# bootloader_burner.net
KiCad netlist of a schematic drawn in EAGLE
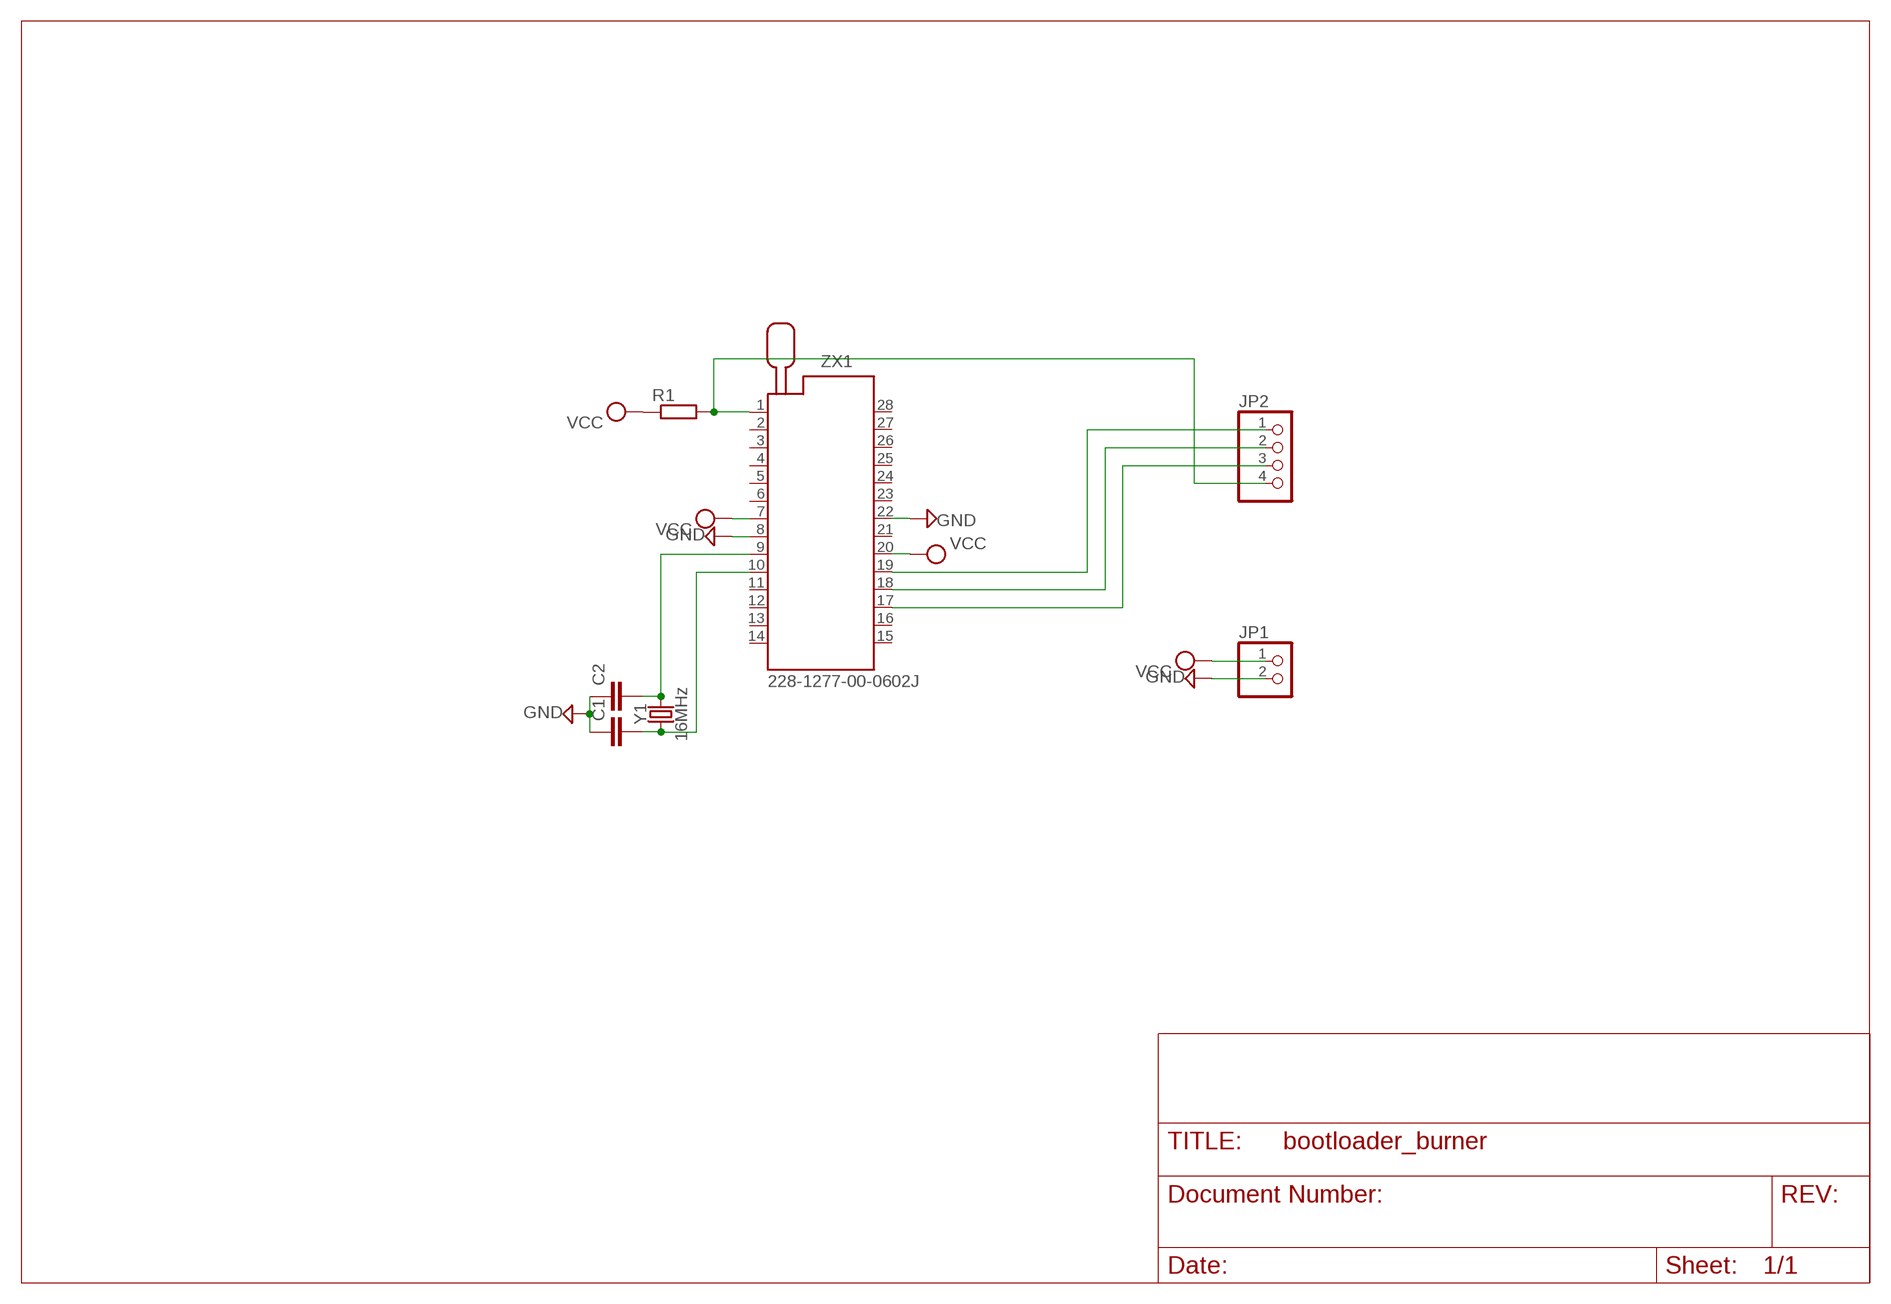
[diagram p0: schematic, sheet 1]

(export (version "E")
  (design (tool "Eeschema 10.0.6"))
  (components
    (comp (ref "C1")
      (value "C-EU025-025X050")
      (footprint "eagle-import:C025-025X050")
      (libsource (lib "eagle-import") (part "C-EU025-025X050"))
    )
    (comp (ref "C2")
      (value "C-EU025-025X050")
      (footprint "eagle-import:C025-025X050")
      (libsource (lib "eagle-import") (part "C-EU025-025X050"))
    )
    (comp (ref "JP1")
      (value "PINHD-1X2")
      (footprint "eagle-import:1X02")
      (libsource (lib "eagle-import") (part "PINHD-1X2"))
    )
    (comp (ref "JP2")
      (value "PINHD-1X4")
      (footprint "eagle-import:1X04")
      (libsource (lib "eagle-import") (part "PINHD-1X4"))
    )
    (comp (ref "R1")
      (value "R-EU_0207/10")
      (footprint "eagle-import:0207_10")
      (libsource (lib "eagle-import") (part "R-EU_0207/10"))
    )
    (comp (ref "Y1")
      (value "16MHz")
      (footprint "eagle-import:HC49US")
      (libsource (lib "eagle-import") (part "CRYSTAL-16MHZPTH-HC49US"))
    )
    (comp (ref "ZX1")
      (value "228-1277-00-0602J")
      (footprint "eagle-import:228-1277-00-0602J")
      (fields (field (name "MF") "3M"))
      (libsource (lib "eagle-import") (part "228-?00-0602J1277-"))
    )
  )
  (nets
    (net (code "1") (name "GND") (class "Default")
      (node (ref "C1") (pin "1") (pinfunction "1_1") (pintype "passive"))
      (node (ref "C2") (pin "1") (pinfunction "1_1") (pintype "passive"))
      (node (ref "JP1") (pin "2") (pinfunction "2_2") (pintype "passive"))
      (node (ref "ZX1") (pin "22") (pinfunction "22_22") (pintype "passive"))
      (node (ref "ZX1") (pin "8") (pinfunction "8_8") (pintype "passive"))
    )
    (net (code "2") (name "Net-(C1-Pad2)") (class "Default")
      (node (ref "C1") (pin "2") (pinfunction "2_2") (pintype "passive"))
      (node (ref "Y1") (pin "1") (pinfunction "1_1") (pintype "passive"))
      (node (ref "ZX1") (pin "10") (pinfunction "10_10") (pintype "passive"))
    )
    (net (code "3") (name "Net-(C2-Pad2)") (class "Default")
      (node (ref "C2") (pin "2") (pinfunction "2_2") (pintype "passive"))
      (node (ref "Y1") (pin "2") (pinfunction "2_2") (pintype "passive"))
      (node (ref "ZX1") (pin "9") (pinfunction "9_9") (pintype "passive"))
    )
    (net (code "4") (name "Net-(JP2-Pad1)") (class "Default")
      (node (ref "JP2") (pin "1") (pinfunction "1_1") (pintype "passive"))
      (node (ref "ZX1") (pin "19") (pinfunction "19_19") (pintype "passive"))
    )
    (net (code "5") (name "Net-(JP2-Pad2)") (class "Default")
      (node (ref "JP2") (pin "2") (pinfunction "2_2") (pintype "passive"))
      (node (ref "ZX1") (pin "18") (pinfunction "18_18") (pintype "passive"))
    )
    (net (code "6") (name "Net-(JP2-Pad3)") (class "Default")
      (node (ref "JP2") (pin "3") (pinfunction "3_3") (pintype "passive"))
      (node (ref "ZX1") (pin "17") (pinfunction "17_17") (pintype "passive"))
    )
    (net (code "7") (name "Net-(JP2-Pad4)") (class "Default")
      (node (ref "JP2") (pin "4") (pinfunction "4_4") (pintype "passive"))
      (node (ref "R1") (pin "2") (pinfunction "2_2") (pintype "passive"))
      (node (ref "ZX1") (pin "1") (pinfunction "1_1") (pintype "passive"))
    )
    (net (code "8") (name "VCC") (class "Default")
      (node (ref "JP1") (pin "1") (pinfunction "1_1") (pintype "passive"))
      (node (ref "R1") (pin "1") (pinfunction "1_1") (pintype "passive"))
      (node (ref "ZX1") (pin "20") (pinfunction "20_20") (pintype "passive"))
      (node (ref "ZX1") (pin "7") (pinfunction "7_7") (pintype "passive"))
    )
    (net (code "9") (name "unconnected-(ZX1-Pad2)") (class "Default")
      (node (ref "ZX1") (pin "2") (pinfunction "2_2") (pintype "passive"))
    )
    (net (code "10") (name "unconnected-(ZX1-Pad3)") (class "Default")
      (node (ref "ZX1") (pin "3") (pinfunction "3_3") (pintype "passive"))
    )
    (net (code "11") (name "unconnected-(ZX1-Pad4)") (class "Default")
      (node (ref "ZX1") (pin "4") (pinfunction "4_4") (pintype "passive"))
    )
    (net (code "12") (name "unconnected-(ZX1-Pad5)") (class "Default")
      (node (ref "ZX1") (pin "5") (pinfunction "5_5") (pintype "passive"))
    )
    (net (code "13") (name "unconnected-(ZX1-Pad6)") (class "Default")
      (node (ref "ZX1") (pin "6") (pinfunction "6_6") (pintype "passive"))
    )
    (net (code "14") (name "unconnected-(ZX1-Pad11)") (class "Default")
      (node (ref "ZX1") (pin "11") (pinfunction "11_11") (pintype "passive"))
    )
    (net (code "15") (name "unconnected-(ZX1-Pad12)") (class "Default")
      (node (ref "ZX1") (pin "12") (pinfunction "12_12") (pintype "passive"))
    )
    (net (code "16") (name "unconnected-(ZX1-Pad13)") (class "Default")
      (node (ref "ZX1") (pin "13") (pinfunction "13_13") (pintype "passive"))
    )
    (net (code "17") (name "unconnected-(ZX1-Pad14)") (class "Default")
      (node (ref "ZX1") (pin "14") (pinfunction "14_14") (pintype "passive"))
    )
    (net (code "18") (name "unconnected-(ZX1-Pad15)") (class "Default")
      (node (ref "ZX1") (pin "15") (pinfunction "15_15") (pintype "passive"))
    )
    (net (code "19") (name "unconnected-(ZX1-Pad16)") (class "Default")
      (node (ref "ZX1") (pin "16") (pinfunction "16_16") (pintype "passive"))
    )
    (net (code "20") (name "unconnected-(ZX1-Pad21)") (class "Default")
      (node (ref "ZX1") (pin "21") (pinfunction "21_21") (pintype "passive"))
    )
    (net (code "21") (name "unconnected-(ZX1-Pad23)") (class "Default")
      (node (ref "ZX1") (pin "23") (pinfunction "23_23") (pintype "passive"))
    )
    (net (code "22") (name "unconnected-(ZX1-Pad24)") (class "Default")
      (node (ref "ZX1") (pin "24") (pinfunction "24_24") (pintype "passive"))
    )
    (net (code "23") (name "unconnected-(ZX1-Pad25)") (class "Default")
      (node (ref "ZX1") (pin "25") (pinfunction "25_25") (pintype "passive"))
    )
    (net (code "24") (name "unconnected-(ZX1-Pad26)") (class "Default")
      (node (ref "ZX1") (pin "26") (pinfunction "26_26") (pintype "passive"))
    )
    (net (code "25") (name "unconnected-(ZX1-Pad27)") (class "Default")
      (node (ref "ZX1") (pin "27") (pinfunction "27_27") (pintype "passive"))
    )
    (net (code "26") (name "unconnected-(ZX1-Pad28)") (class "Default")
      (node (ref "ZX1") (pin "28") (pinfunction "28_28") (pintype "passive"))
    )
  )
)
